# Puzzle_I2C_Motor_Driver_v0_92.net
KiCad netlist of a schematic drawn in EAGLE
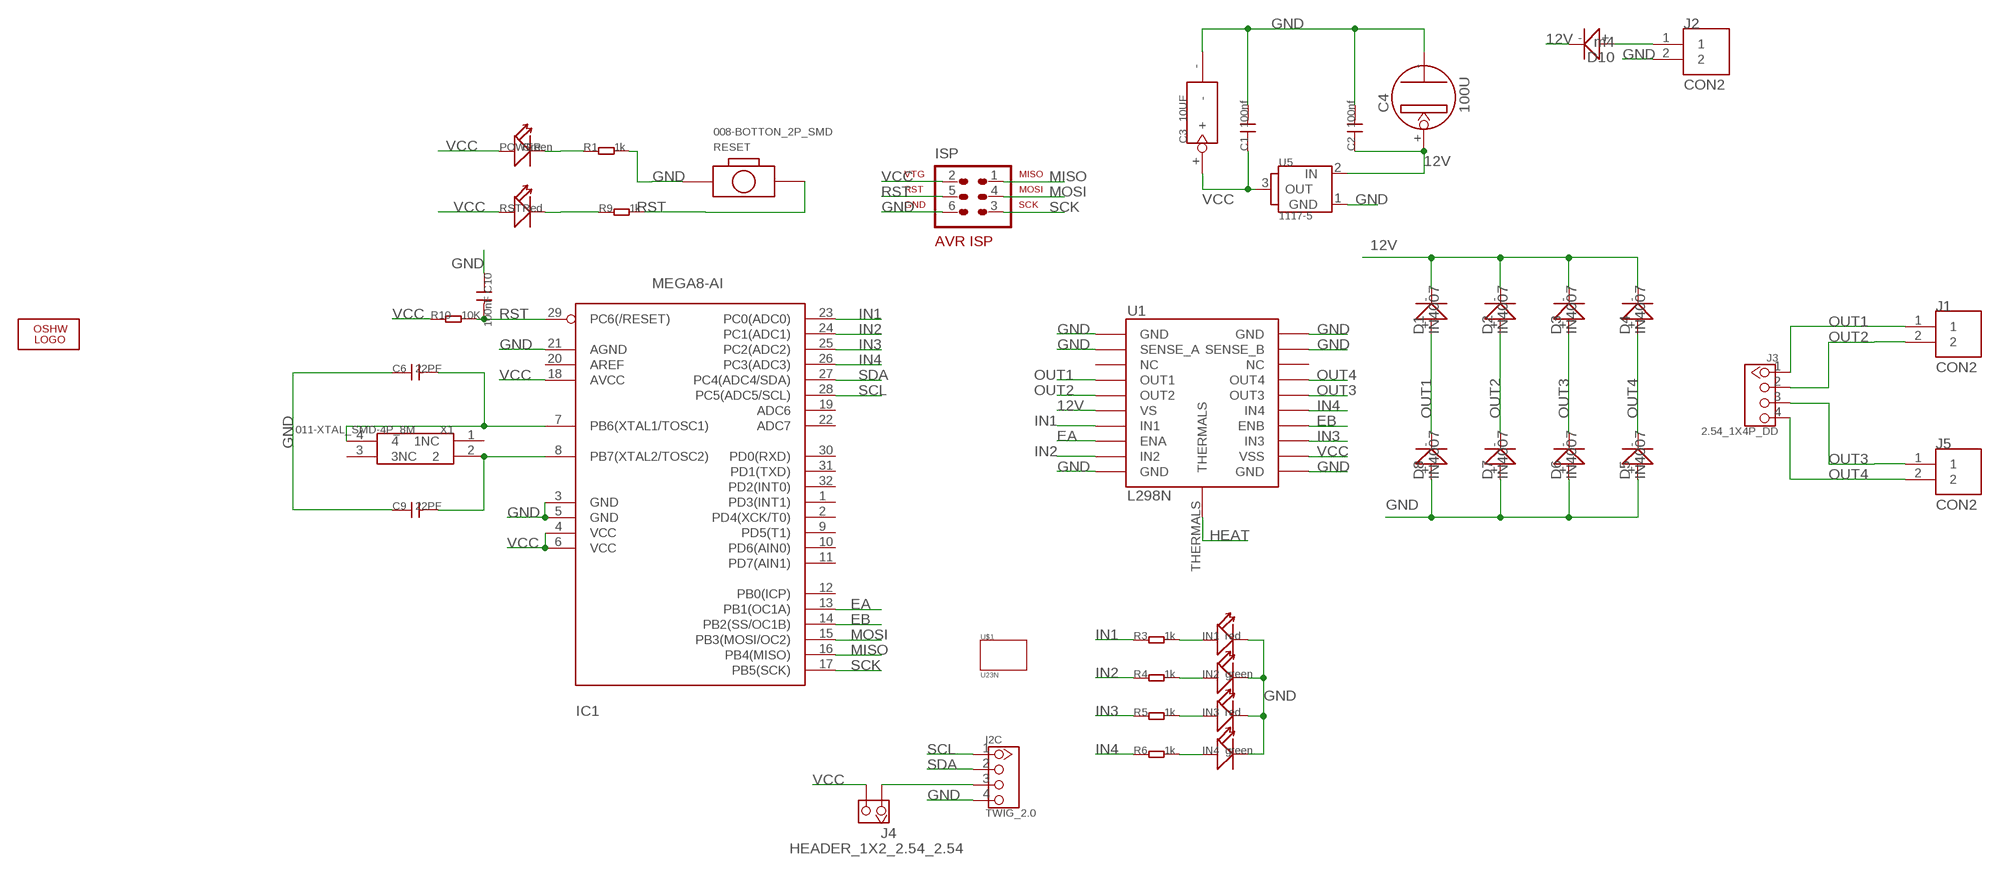
[diagram p0: schematic, sheet 1]

(export (version "E")
  (design (tool "Eeschema 10.0.6"))
  (components
    (comp (ref "C1")
      (value "100nf")
      (footprint "eagle-import:0603_S")
      (libsource (lib "eagle-import") (part "006-C3035"))
    )
    (comp (ref "C2")
      (value "100nf")
      (footprint "eagle-import:0603_S")
      (libsource (lib "eagle-import") (part "006-C3035"))
    )
    (comp (ref "C3")
      (value "10UF")
      (footprint "eagle-import:C_TAN_3X3.5")
      (libsource (lib "eagle-import") (part "C_TAN_B"))
    )
    (comp (ref "C4")
      (value "100U")
      (footprint "eagle-import:SANYO-OSCON_SMD_C6")
      (libsource (lib "eagle-import") (part "PANASONIC_D260"))
    )
    (comp (ref "C6")
      (value "22PF")
      (footprint "eagle-import:0603_S")
      (libsource (lib "eagle-import") (part "006-C3035"))
    )
    (comp (ref "C9")
      (value "22PF")
      (footprint "eagle-import:0603_S")
      (libsource (lib "eagle-import") (part "006-C3035"))
    )
    (comp (ref "C10")
      (value "100nF")
      (footprint "eagle-import:0603_S")
      (libsource (lib "eagle-import") (part "006-C3035"))
    )
    (comp (ref "D1")
      (value "IN4007")
      (footprint "eagle-import:D2010")
      (libsource (lib "eagle-import") (part "010-D2010"))
    )
    (comp (ref "D2")
      (value "IN4007")
      (footprint "eagle-import:D2010")
      (libsource (lib "eagle-import") (part "010-D2010"))
    )
    (comp (ref "D3")
      (value "IN4007")
      (footprint "eagle-import:D2010")
      (libsource (lib "eagle-import") (part "010-D2010"))
    )
    (comp (ref "D4")
      (value "IN4007")
      (footprint "eagle-import:D2010")
      (libsource (lib "eagle-import") (part "010-D2010"))
    )
    (comp (ref "D5")
      (value "IN4007")
      (footprint "eagle-import:D2010")
      (libsource (lib "eagle-import") (part "010-D2010"))
    )
    (comp (ref "D6")
      (value "IN4007")
      (footprint "eagle-import:D2010")
      (libsource (lib "eagle-import") (part "010-D2010"))
    )
    (comp (ref "D7")
      (value "IN4007")
      (footprint "eagle-import:D2010")
      (libsource (lib "eagle-import") (part "010-D2010"))
    )
    (comp (ref "D8")
      (value "IN4007")
      (footprint "eagle-import:D2010")
      (libsource (lib "eagle-import") (part "010-D2010"))
    )
    (comp (ref "D10")
      (value "m4")
      (footprint "eagle-import:D2010")
      (libsource (lib "eagle-import") (part "010-D2010"))
    )
    (comp (ref "I2C")
      (value "TWIG_2.0")
      (footprint "eagle-import:2.0_1X4")
      (libsource (lib "eagle-import") (part "TWIG_2.0"))
    )
    (comp (ref "IC1")
      (value "MEGA8-AI")
      (footprint "eagle-import:TQFP32-08")
      (libsource (lib "eagle-import") (part "MEGA8-AI"))
    )
    (comp (ref "IN1")
      (value "red")
      (footprint "eagle-import:D0603")
      (libsource (lib "eagle-import") (part "007-LED0603"))
    )
    (comp (ref "IN2")
      (value "green")
      (footprint "eagle-import:D0603")
      (libsource (lib "eagle-import") (part "007-LED0603"))
    )
    (comp (ref "IN3")
      (value "red")
      (footprint "eagle-import:D0603")
      (libsource (lib "eagle-import") (part "007-LED0603"))
    )
    (comp (ref "IN4")
      (value "green")
      (footprint "eagle-import:D0603")
      (libsource (lib "eagle-import") (part "007-LED0603"))
    )
    (comp (ref "ISP")
      (value "AVR-ISP-6")
      (footprint "eagle-import:AVR-ISP-6")
      (libsource (lib "eagle-import") (part "AVR-ISP-6"))
    )
    (comp (ref "J1")
      (value "CON2")
      (footprint "eagle-import:CON2")
      (libsource (lib "eagle-import") (part "CON2"))
    )
    (comp (ref "J2")
      (value "CON2")
      (footprint "eagle-import:CON2")
      (libsource (lib "eagle-import") (part "CON2"))
    )
    (comp (ref "J3")
      (value "2.54_1X4P_DD")
      (footprint "eagle-import:CK_1X4")
      (libsource (lib "eagle-import") (part "2.54_1X4P_DD"))
    )
    (comp (ref "J4")
      (value "HEADER_1X2_2.54_2.54")
      (footprint "eagle-import:65_35")
      (libsource (lib "eagle-import") (part "HEADER_1X2_2.54_2.54"))
    )
    (comp (ref "J5")
      (value "CON2")
      (footprint "eagle-import:CON2")
      (libsource (lib "eagle-import") (part "CON2"))
    )
    (comp (ref "LOGO2")
      (value "LOGO-OSHW-FILLX0200-NT")
      (footprint "eagle-import:OSHW_FILLX200_NOTEXT")
      (libsource (lib "eagle-import") (part "LOGO-OSHW-FILLX0200-NT"))
    )
    (comp (ref "POWER")
      (value "Green")
      (footprint "eagle-import:D0603")
      (libsource (lib "eagle-import") (part "007-LED0603"))
    )
    (comp (ref "R1")
      (value "1k")
      (footprint "eagle-import:0603-1")
      (libsource (lib "eagle-import") (part "005-R0603"))
    )
    (comp (ref "R3")
      (value "1k")
      (footprint "eagle-import:0603-1")
      (libsource (lib "eagle-import") (part "005-R0603"))
    )
    (comp (ref "R4")
      (value "1k")
      (footprint "eagle-import:0603-1")
      (libsource (lib "eagle-import") (part "005-R0603"))
    )
    (comp (ref "R5")
      (value "1k")
      (footprint "eagle-import:0603-1")
      (libsource (lib "eagle-import") (part "005-R0603"))
    )
    (comp (ref "R6")
      (value "1k")
      (footprint "eagle-import:0603-1")
      (libsource (lib "eagle-import") (part "005-R0603"))
    )
    (comp (ref "R9")
      (value "1k")
      (footprint "eagle-import:0603-1")
      (libsource (lib "eagle-import") (part "005-R0603"))
    )
    (comp (ref "R10")
      (value "10K")
      (footprint "eagle-import:0603-1")
      (libsource (lib "eagle-import") (part "005-R0603"))
    )
    (comp (ref "RESET")
      (value "008-BOTTON_2P_SMD")
      (footprint "eagle-import:BOTTON_1")
      (libsource (lib "eagle-import") (part "008-BOTTON_2P_SMD"))
    )
    (comp (ref "RST")
      (value "Red")
      (footprint "eagle-import:D0603")
      (libsource (lib "eagle-import") (part "007-LED0603"))
    )
    (comp (ref "U$1")
      (value "U23N")
      (footprint "eagle-import:U2_3N")
      (libsource (lib "eagle-import") (part "U23N"))
    )
    (comp (ref "U1")
      (value "L298N")
      (footprint "eagle-import:POWERSO20")
      (libsource (lib "eagle-import") (part "L298_BRIDGE_DRIVER"))
    )
    (comp (ref "U5")
      (value "1117-5")
      (footprint "eagle-import:TO252")
      (libsource (lib "eagle-import") (part "1117-5"))
    )
    (comp (ref "X1")
      (value "011-XTAL_SMD-4P_8M")
      (footprint "eagle-import:CRYSTAL-SMD-5X3")
      (libsource (lib "eagle-import") (part "011-XTAL_SMD-4P"))
    )
  )
  (nets
    (net (code "1") (name "/12V") (class "Default")
      (node (ref "C2") (pin "1") (pinfunction "1_1") (pintype "passive"))
      (node (ref "C4") (pin "+") (pinfunction "+_+") (pintype "bidirectional"))
      (node (ref "D1") (pin "-") (pinfunction "-_-") (pintype "passive"))
      (node (ref "D10") (pin "-") (pinfunction "-_-") (pintype "passive"))
      (node (ref "D2") (pin "-") (pinfunction "-_-") (pintype "passive"))
      (node (ref "D3") (pin "-") (pinfunction "-_-") (pintype "passive"))
      (node (ref "D4") (pin "-") (pinfunction "-_-") (pintype "passive"))
      (node (ref "U1") (pin "P$6") (pinfunction "VS_P$6") (pintype "bidirectional"))
      (node (ref "U5") (pin "2") (pinfunction "IN_2") (pintype "bidirectional"))
    )
    (net (code "2") (name "/EA") (class "Default")
      (node (ref "IC1") (pin "13") (pinfunction "PB1(OC1A)_13") (pintype "bidirectional"))
      (node (ref "U1") (pin "P$8") (pinfunction "ENA_P$8") (pintype "bidirectional"))
    )
    (net (code "3") (name "/EB") (class "Default")
      (node (ref "IC1") (pin "14") (pinfunction "PB2(SS/OC1B)_14") (pintype "bidirectional"))
      (node (ref "U1") (pin "P$14") (pinfunction "ENB_P$14") (pintype "bidirectional"))
    )
    (net (code "4") (name "/GND") (class "Default")
      (node (ref "C1") (pin "2") (pinfunction "2_2") (pintype "passive"))
      (node (ref "C10") (pin "1") (pinfunction "1_1") (pintype "passive"))
      (node (ref "C2") (pin "2") (pinfunction "2_2") (pintype "passive"))
      (node (ref "C3") (pin "-") (pinfunction "-_-") (pintype "bidirectional"))
      (node (ref "C4") (pin "-") (pinfunction "-_-") (pintype "bidirectional"))
      (node (ref "C6") (pin "1") (pinfunction "1_1") (pintype "passive"))
      (node (ref "C9") (pin "1") (pinfunction "1_1") (pintype "passive"))
      (node (ref "D5") (pin "+") (pinfunction "+_+") (pintype "passive"))
      (node (ref "D6") (pin "+") (pinfunction "+_+") (pintype "passive"))
      (node (ref "D7") (pin "+") (pinfunction "+_+") (pintype "passive"))
      (node (ref "D8") (pin "+") (pinfunction "+_+") (pintype "passive"))
      (node (ref "I2C") (pin "4") (pinfunction "4_4") (pintype "bidirectional"))
      (node (ref "IC1") (pin "21") (pinfunction "AGND_21") (pintype "bidirectional"))
      (node (ref "IC1") (pin "3") (pinfunction "GND_3") (pintype "bidirectional"))
      (node (ref "IC1") (pin "5") (pinfunction "GND_5") (pintype "bidirectional"))
      (node (ref "IN1") (pin "-") (pinfunction "-_-") (pintype "passive"))
      (node (ref "IN2") (pin "-") (pinfunction "-_-") (pintype "passive"))
      (node (ref "IN3") (pin "-") (pinfunction "-_-") (pintype "passive"))
      (node (ref "IN4") (pin "-") (pinfunction "-_-") (pintype "passive"))
      (node (ref "ISP") (pin "6") (pinfunction "6_6") (pintype "passive"))
      (node (ref "J2") (pin "2") (pinfunction "2_2") (pintype "bidirectional"))
      (node (ref "R1") (pin "2") (pinfunction "2_2") (pintype "passive"))
      (node (ref "RESET") (pin "1") (pinfunction "1_1") (pintype "bidirectional"))
      (node (ref "U1") (pin "P$1") (pinfunction "GND_P$1") (pintype "bidirectional"))
      (node (ref "U1") (pin "P$10") (pinfunction "GND_P$10") (pintype "bidirectional"))
      (node (ref "U1") (pin "P$11") (pinfunction "GND_P$11") (pintype "bidirectional"))
      (node (ref "U1") (pin "P$19") (pinfunction "SENSE_B_P$19") (pintype "bidirectional"))
      (node (ref "U1") (pin "P$2") (pinfunction "SENSE_A_P$2") (pintype "bidirectional"))
      (node (ref "U1") (pin "P$20") (pinfunction "GND_P$20") (pintype "bidirectional"))
      (node (ref "U5") (pin "1") (pinfunction "GND_1") (pintype "bidirectional"))
    )
    (net (code "5") (name "/HEAT") (class "Default")
      (node (ref "U1") (pin "THERMALS") (pinfunction "THERMALS_THERMALS") (pintype "bidirectional"))
    )
    (net (code "6") (name "/IN1") (class "Default")
      (node (ref "IC1") (pin "23") (pinfunction "PC0(ADC0)_23") (pintype "bidirectional"))
      (node (ref "R3") (pin "1") (pinfunction "1_1") (pintype "passive"))
      (node (ref "U1") (pin "P$7") (pinfunction "IN1_P$7") (pintype "bidirectional"))
    )
    (net (code "7") (name "/IN2") (class "Default")
      (node (ref "IC1") (pin "24") (pinfunction "PC1(ADC1)_24") (pintype "bidirectional"))
      (node (ref "R4") (pin "1") (pinfunction "1_1") (pintype "passive"))
      (node (ref "U1") (pin "P$9") (pinfunction "IN2_P$9") (pintype "bidirectional"))
    )
    (net (code "8") (name "/IN3") (class "Default")
      (node (ref "IC1") (pin "25") (pinfunction "PC2(ADC2)_25") (pintype "bidirectional"))
      (node (ref "R5") (pin "1") (pinfunction "1_1") (pintype "passive"))
      (node (ref "U1") (pin "P$13") (pinfunction "IN3_P$13") (pintype "bidirectional"))
    )
    (net (code "9") (name "/IN4") (class "Default")
      (node (ref "IC1") (pin "26") (pinfunction "PC3(ADC3)_26") (pintype "bidirectional"))
      (node (ref "R6") (pin "1") (pinfunction "1_1") (pintype "passive"))
      (node (ref "U1") (pin "P$15") (pinfunction "IN4_P$15") (pintype "bidirectional"))
    )
    (net (code "10") (name "/MISO") (class "Default")
      (node (ref "IC1") (pin "16") (pinfunction "PB4(MISO)_16") (pintype "bidirectional"))
      (node (ref "ISP") (pin "1") (pinfunction "1_1") (pintype "passive"))
    )
    (net (code "11") (name "/MOSI") (class "Default")
      (node (ref "IC1") (pin "15") (pinfunction "PB3(MOSI/OC2)_15") (pintype "bidirectional"))
      (node (ref "ISP") (pin "4") (pinfunction "4_4") (pintype "passive"))
    )
    (net (code "12") (name "/OUT1") (class "Default")
      (node (ref "D1") (pin "+") (pinfunction "+_+") (pintype "passive"))
      (node (ref "D8") (pin "-") (pinfunction "-_-") (pintype "passive"))
      (node (ref "J1") (pin "1") (pinfunction "1_1") (pintype "bidirectional"))
      (node (ref "J3") (pin "1") (pinfunction "P$1_1") (pintype "bidirectional"))
      (node (ref "U1") (pin "P$4") (pinfunction "OUT1_P$4") (pintype "bidirectional"))
    )
    (net (code "13") (name "/OUT2") (class "Default")
      (node (ref "D2") (pin "+") (pinfunction "+_+") (pintype "passive"))
      (node (ref "D7") (pin "-") (pinfunction "-_-") (pintype "passive"))
      (node (ref "J1") (pin "2") (pinfunction "2_2") (pintype "bidirectional"))
      (node (ref "J3") (pin "2") (pinfunction "P$2_2") (pintype "bidirectional"))
      (node (ref "U1") (pin "P$5") (pinfunction "OUT2_P$5") (pintype "bidirectional"))
    )
    (net (code "14") (name "/OUT3") (class "Default")
      (node (ref "D3") (pin "+") (pinfunction "+_+") (pintype "passive"))
      (node (ref "D6") (pin "-") (pinfunction "-_-") (pintype "passive"))
      (node (ref "J3") (pin "3") (pinfunction "P$3_3") (pintype "bidirectional"))
      (node (ref "J5") (pin "1") (pinfunction "1_1") (pintype "bidirectional"))
      (node (ref "U1") (pin "P$16") (pinfunction "OUT3_P$16") (pintype "bidirectional"))
    )
    (net (code "15") (name "/OUT4") (class "Default")
      (node (ref "D4") (pin "+") (pinfunction "+_+") (pintype "passive"))
      (node (ref "D5") (pin "-") (pinfunction "-_-") (pintype "passive"))
      (node (ref "J3") (pin "4") (pinfunction "P$4_4") (pintype "bidirectional"))
      (node (ref "J5") (pin "2") (pinfunction "2_2") (pintype "bidirectional"))
      (node (ref "U1") (pin "P$17") (pinfunction "OUT4_P$17") (pintype "bidirectional"))
    )
    (net (code "16") (name "/RST") (class "Default")
      (node (ref "C10") (pin "2") (pinfunction "2_2") (pintype "passive"))
      (node (ref "IC1") (pin "29") (pinfunction "PC6(/RESET)_29") (pintype "bidirectional"))
      (node (ref "ISP") (pin "5") (pinfunction "5_5") (pintype "passive"))
      (node (ref "R10") (pin "2") (pinfunction "2_2") (pintype "passive"))
      (node (ref "R9") (pin "2") (pinfunction "2_2") (pintype "passive"))
      (node (ref "RESET") (pin "P$2") (pinfunction "2_P$2") (pintype "bidirectional"))
    )
    (net (code "17") (name "/SCK") (class "Default")
      (node (ref "IC1") (pin "17") (pinfunction "PB5(SCK)_17") (pintype "bidirectional"))
      (node (ref "ISP") (pin "3") (pinfunction "3_3") (pintype "passive"))
    )
    (net (code "18") (name "/SCL") (class "Default")
      (node (ref "I2C") (pin "1") (pinfunction "1_1") (pintype "bidirectional"))
      (node (ref "IC1") (pin "28") (pinfunction "PC5(ADC5/SCL)_28") (pintype "bidirectional"))
    )
    (net (code "19") (name "/SDA") (class "Default")
      (node (ref "I2C") (pin "2") (pinfunction "2_2") (pintype "bidirectional"))
      (node (ref "IC1") (pin "27") (pinfunction "PC4(ADC4/SDA)_27") (pintype "bidirectional"))
    )
    (net (code "20") (name "/VCC") (class "Default")
      (node (ref "C1") (pin "1") (pinfunction "1_1") (pintype "passive"))
      (node (ref "C3") (pin "+") (pinfunction "+_+") (pintype "bidirectional"))
      (node (ref "IC1") (pin "18") (pinfunction "AVCC_18") (pintype "bidirectional"))
      (node (ref "IC1") (pin "4") (pinfunction "VCC_4") (pintype "bidirectional"))
      (node (ref "IC1") (pin "6") (pinfunction "VCC_6") (pintype "bidirectional"))
      (node (ref "ISP") (pin "2") (pinfunction "2_2") (pintype "passive"))
      (node (ref "J4") (pin "2") (pinfunction "2_2") (pintype "bidirectional"))
      (node (ref "POWER") (pin "+") (pinfunction "+_+") (pintype "passive"))
      (node (ref "R10") (pin "1") (pinfunction "1_1") (pintype "passive"))
      (node (ref "RST") (pin "+") (pinfunction "+_+") (pintype "passive"))
      (node (ref "U1") (pin "P$12") (pinfunction "VSS_P$12") (pintype "bidirectional"))
      (node (ref "U5") (pin "3") (pinfunction "OUT_3") (pintype "bidirectional"))
    )
    (net (code "21") (name "Net-(D10-Pad+)") (class "Default")
      (node (ref "D10") (pin "+") (pinfunction "+_+") (pintype "passive"))
      (node (ref "J2") (pin "1") (pinfunction "1_1") (pintype "bidirectional"))
    )
    (net (code "22") (name "Net-(I2C-Pad3)") (class "Default")
      (node (ref "I2C") (pin "3") (pinfunction "3_3") (pintype "bidirectional"))
      (node (ref "J4") (pin "1") (pinfunction "1_1") (pintype "bidirectional"))
    )
    (net (code "23") (name "Net-(IC1-PB6(XTAL1{slash}TOSC1))") (class "Default")
      (node (ref "C6") (pin "2") (pinfunction "2_2") (pintype "passive"))
      (node (ref "IC1") (pin "7") (pinfunction "PB6(XTAL1/TOSC1)_7") (pintype "bidirectional"))
      (node (ref "X1") (pin "4") (pinfunction "4_4") (pintype "bidirectional"))
    )
    (net (code "24") (name "Net-(IC1-PB7(XTAL2{slash}TOSC2))") (class "Default")
      (node (ref "C9") (pin "2") (pinfunction "2_2") (pintype "passive"))
      (node (ref "IC1") (pin "8") (pinfunction "PB7(XTAL2/TOSC2)_8") (pintype "bidirectional"))
      (node (ref "X1") (pin "2") (pinfunction "2_2") (pintype "bidirectional"))
    )
    (net (code "25") (name "Net-(IN1-Pad+)") (class "Default")
      (node (ref "IN1") (pin "+") (pinfunction "+_+") (pintype "passive"))
      (node (ref "R3") (pin "2") (pinfunction "2_2") (pintype "passive"))
    )
    (net (code "26") (name "Net-(IN2-Pad+)") (class "Default")
      (node (ref "IN2") (pin "+") (pinfunction "+_+") (pintype "passive"))
      (node (ref "R4") (pin "2") (pinfunction "2_2") (pintype "passive"))
    )
    (net (code "27") (name "Net-(IN3-Pad+)") (class "Default")
      (node (ref "IN3") (pin "+") (pinfunction "+_+") (pintype "passive"))
      (node (ref "R5") (pin "2") (pinfunction "2_2") (pintype "passive"))
    )
    (net (code "28") (name "Net-(IN4-Pad+)") (class "Default")
      (node (ref "IN4") (pin "+") (pinfunction "+_+") (pintype "passive"))
      (node (ref "R6") (pin "2") (pinfunction "2_2") (pintype "passive"))
    )
    (net (code "29") (name "Net-(POWER-Pad-)") (class "Default")
      (node (ref "POWER") (pin "-") (pinfunction "-_-") (pintype "passive"))
      (node (ref "R1") (pin "1") (pinfunction "1_1") (pintype "passive"))
    )
    (net (code "30") (name "Net-(R9-Pad1)") (class "Default")
      (node (ref "R9") (pin "1") (pinfunction "1_1") (pintype "passive"))
      (node (ref "RST") (pin "-") (pinfunction "-_-") (pintype "passive"))
    )
    (net (code "31") (name "unconnected-(IC1-ADC6-Pad19)") (class "Default")
      (node (ref "IC1") (pin "19") (pinfunction "ADC6_19") (pintype "bidirectional"))
    )
    (net (code "32") (name "unconnected-(IC1-ADC7-Pad22)") (class "Default")
      (node (ref "IC1") (pin "22") (pinfunction "ADC7_22") (pintype "bidirectional"))
    )
    (net (code "33") (name "unconnected-(IC1-AREF-Pad20)") (class "Default")
      (node (ref "IC1") (pin "20") (pinfunction "AREF_20") (pintype "bidirectional"))
    )
    (net (code "34") (name "unconnected-(IC1-PB0(ICP)-Pad12)") (class "Default")
      (node (ref "IC1") (pin "12") (pinfunction "PB0(ICP)_12") (pintype "bidirectional"))
    )
    (net (code "35") (name "unconnected-(IC1-PD0(RXD)-Pad30)") (class "Default")
      (node (ref "IC1") (pin "30") (pinfunction "PD0(RXD)_30") (pintype "bidirectional"))
    )
    (net (code "36") (name "unconnected-(IC1-PD1(TXD)-Pad31)") (class "Default")
      (node (ref "IC1") (pin "31") (pinfunction "PD1(TXD)_31") (pintype "bidirectional"))
    )
    (net (code "37") (name "unconnected-(IC1-PD2(INT0)-Pad32)") (class "Default")
      (node (ref "IC1") (pin "32") (pinfunction "PD2(INT0)_32") (pintype "bidirectional"))
    )
    (net (code "38") (name "unconnected-(IC1-PD3(INT1)-Pad1)") (class "Default")
      (node (ref "IC1") (pin "1") (pinfunction "PD3(INT1)_1") (pintype "bidirectional"))
    )
    (net (code "39") (name "unconnected-(IC1-PD4(XCK{slash}T0)-Pad2)") (class "Default")
      (node (ref "IC1") (pin "2") (pinfunction "PD4(XCK/T0)_2") (pintype "bidirectional"))
    )
    (net (code "40") (name "unconnected-(IC1-PD5(T1)-Pad9)") (class "Default")
      (node (ref "IC1") (pin "9") (pinfunction "PD5(T1)_9") (pintype "bidirectional"))
    )
    (net (code "41") (name "unconnected-(IC1-PD6(AIN0)-Pad10)") (class "Default")
      (node (ref "IC1") (pin "10") (pinfunction "PD6(AIN0)_10") (pintype "bidirectional"))
    )
    (net (code "42") (name "unconnected-(IC1-PD7(AIN1)-Pad11)") (class "Default")
      (node (ref "IC1") (pin "11") (pinfunction "PD7(AIN1)_11") (pintype "bidirectional"))
    )
    (net (code "43") (name "unconnected-(U1-NC-PadP$3)") (class "Default")
      (node (ref "U1") (pin "P$3") (pinfunction "NC_P$3") (pintype "bidirectional"))
    )
    (net (code "44") (name "unconnected-(U1-NC-PadP$18)") (class "Default")
      (node (ref "U1") (pin "P$18") (pinfunction "NC_P$18") (pintype "bidirectional"))
    )
    (net (code "45") (name "unconnected-(X1-1NC-Pad1)") (class "Default")
      (node (ref "X1") (pin "1") (pinfunction "1NC_1") (pintype "bidirectional"))
    )
    (net (code "46") (name "unconnected-(X1-3NC-Pad3)") (class "Default")
      (node (ref "X1") (pin "3") (pinfunction "3NC_3") (pintype "bidirectional"))
    )
  )
)
